# H0AR4_Frontend.net
KiCad netlist of a schematic drawn in Altium Designer
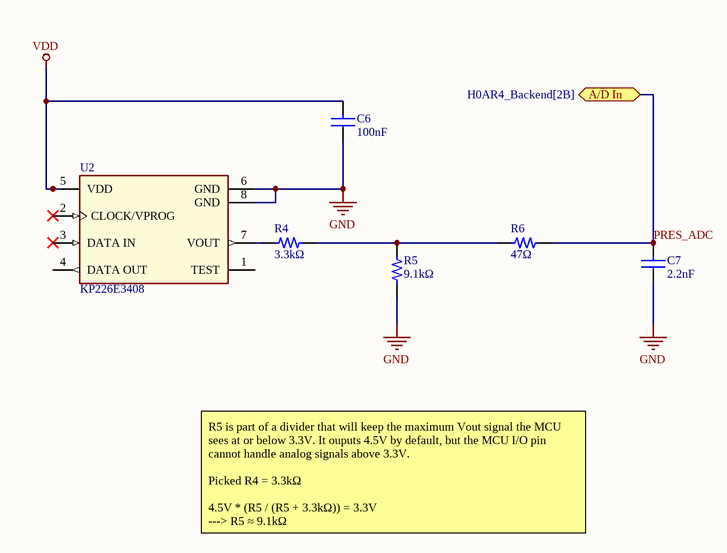
[diagram p0: H0AR4_Frontend.SchDoc]

(export (version "E")
  (design (tool "Eeschema 10.0.6"))
  (components
    (comp (ref "C6")
      (value "100nF")
      (footprint "C0603")
      (fields
        (field (name "MANUFACTURER") "Samsung Electro-Mechanics")
        (field (name "MANUFACTURER PART NUMBER") "CL10B104KA8NNNC")
        (field (name "TOLERANCE") "10%")
      )
      (libsource (lib "Hexabitz Altium Library") (part "generic Capacitor"))
    )
    (comp (ref "C7")
      (value "2.2nF")
      (footprint "C0603")
      (fields
        (field (name "MANUFACTURER") "Samsung Electro-Mechanics")
        (field (name "MANUFACTURER PART NUMBER") "CL10B104KA8NNNC")
        (field (name "TOLERANCE") "10%")
      )
      (libsource (lib "Hexabitz Altium Library") (part "generic Capacitor"))
    )
    (comp (ref "R4")
      (value "3.3kΩ")
      (footprint "R0603")
      (description "Res Thick Film 0603 270 Ohm 5% 0.1W(1/10W) ±200ppm/C Pad SMD Automotive T/R")
      (fields
        (field (name "MANUFACTURER") "Panasonic")
        (field (name "MANUFACTURER PART NUMBER") "ERJ-3GEYJ271V")
      )
      (libsource (lib "Hexabitz Altium Library") (part "generic Resistor"))
    )
    (comp (ref "R5")
      (value "9.1kΩ")
      (footprint "R0603")
      (description "Res Thick Film 0603 270 Ohm 5% 0.1W(1/10W) ±200ppm/C Pad SMD Automotive T/R")
      (fields
        (field (name "MANUFACTURER") "Panasonic")
        (field (name "MANUFACTURER PART NUMBER") "ERJ-3GEYJ271V")
      )
      (libsource (lib "") (part "generic Resistor_1"))
    )
    (comp (ref "R6")
      (value "47Ω")
      (footprint "R0603")
      (description "Res Thick Film 0603 270 Ohm 5% 0.1W(1/10W) ±200ppm/C Pad SMD Automotive T/R")
      (fields
        (field (name "MANUFACTURER") "Panasonic")
        (field (name "MANUFACTURER PART NUMBER") "ERJ-3GEYJ271V")
      )
      (libsource (lib "Hexabitz Altium Library") (part "generic Resistor"))
    )
    (comp (ref "U2")
      (value "KP226E3408")
      (footprint "SOTFL127P860X290-8N-1-V")
      (description "Analog Absolute Pressure Sensor, Pressure 40 kPa to 115 kPa, Voltage range 1.33V to 4.7V")
      (fields (field (name "MPN") "KP226E3408XTMA1") (field (name "MANUFACTURER") "Infineon Technologies"))
      (libsource (lib "Integrated_Library1") (part "KP226E3408"))
    )
  )
  (nets
    (net (code "1") (name "/PRES_ADC") (class "Default")
      (node (ref "C7") (pin "2") (pinfunction "2_2") (pintype "passive"))
      (node (ref "R6") (pin "2") (pinfunction "2_2") (pintype "passive"))
    )
    (net (code "2") (name "GND") (class "Default")
      (node (ref "C6") (pin "1") (pinfunction "1_1") (pintype "passive"))
      (node (ref "C7") (pin "1") (pinfunction "1_1") (pintype "passive"))
      (node (ref "R5") (pin "1") (pinfunction "1_1") (pintype "passive"))
      (node (ref "U2") (pin "6") (pinfunction "GND_6") (pintype "power_in"))
      (node (ref "U2") (pin "8") (pinfunction "GND_8") (pintype "power_in"))
    )
    (net (code "3") (name "Net-(R4-Pad2)") (class "Default")
      (node (ref "R4") (pin "2") (pinfunction "2_2") (pintype "passive"))
      (node (ref "R5") (pin "2") (pinfunction "2_2") (pintype "passive"))
      (node (ref "R6") (pin "1") (pinfunction "1_1") (pintype "passive"))
    )
    (net (code "4") (name "Net-(U2-VOUT)") (class "Default")
      (node (ref "R4") (pin "1") (pinfunction "1_1") (pintype "passive"))
      (node (ref "U2") (pin "7") (pinfunction "VOUT_7") (pintype "output"))
    )
    (net (code "5") (name "VDD") (class "Default")
      (node (ref "C6") (pin "2") (pinfunction "2_2") (pintype "passive"))
      (node (ref "U2") (pin "5") (pinfunction "VDD_5") (pintype "power_in"))
    )
    (net (code "6") (name "unconnected-(U2-CLOCK{slash}VPROG-Pad2)") (class "Default")
      (node (ref "U2") (pin "2") (pinfunction "CLOCK/VPROG_2") (pintype "input+no_connect"))
    )
    (net (code "7") (name "unconnected-(U2-DATA_IN-Pad3)") (class "Default")
      (node (ref "U2") (pin "3") (pinfunction "DATA_IN_3") (pintype "input+no_connect"))
    )
    (net (code "8") (name "unconnected-(U2-DATA_OUT-Pad4)") (class "Default")
      (node (ref "U2") (pin "4") (pinfunction "DATA_OUT_4") (pintype "output"))
    )
    (net (code "9") (name "unconnected-(U2-TEST-Pad1)") (class "Default")
      (node (ref "U2") (pin "1") (pinfunction "TEST_1") (pintype "passive"))
    )
  )
)
